# analog-fan-controller.net
KiCad netlist of a schematic drawn in EAGLE
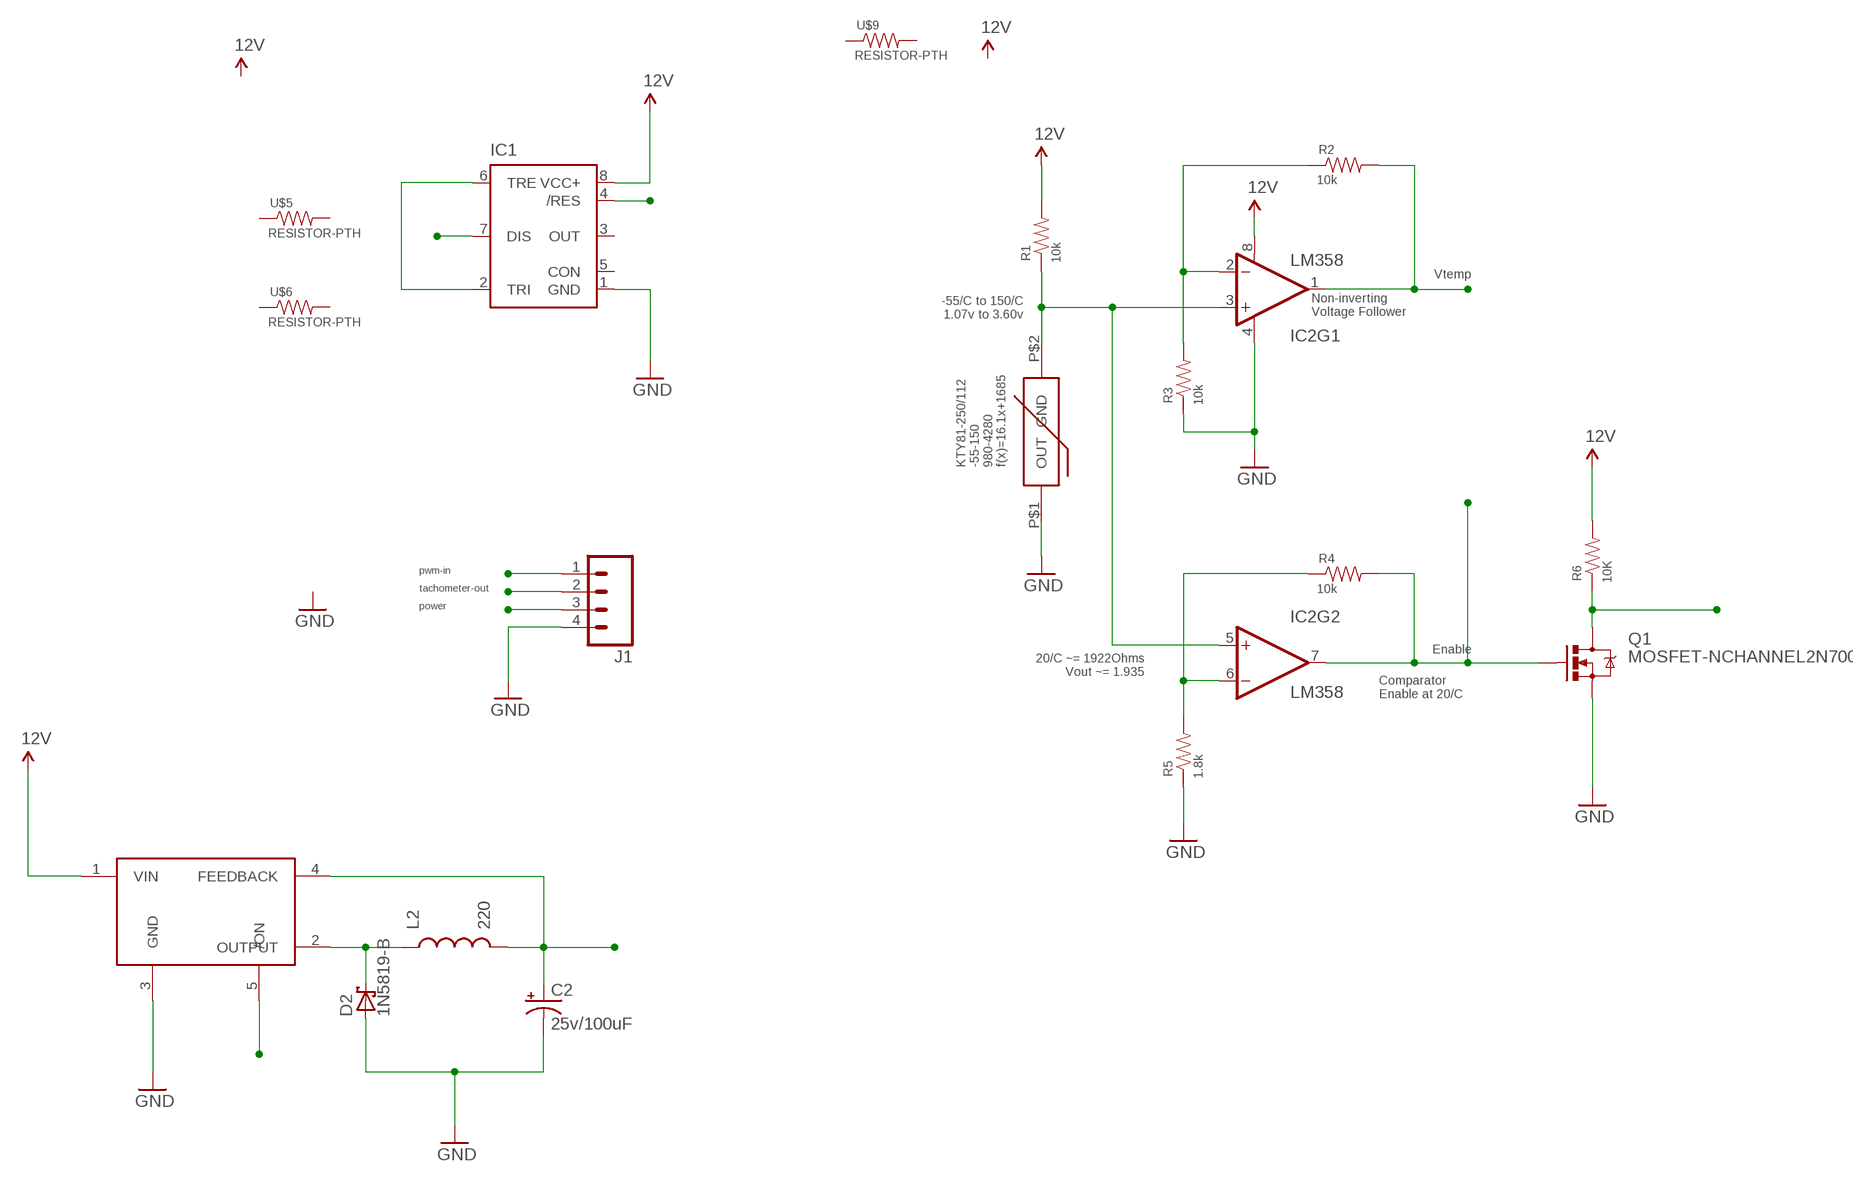
[diagram p0: schematic, sheet 1]

(export (version "E")
  (design (tool "Eeschema 10.0.6"))
  (components
    (comp (ref "C2")
      (value "25v/100uF")
      (footprint "eagle-import:CPOL-RADIAL-1000UF-25V")
      (libsource (lib "eagle-import") (part "1000UF-25V(PTH)"))
    )
    (comp (ref "D2")
      (value "1N5819-B")
      (footprint "eagle-import:DO41-7.6")
      (libsource (lib "eagle-import") (part "1N5819-B"))
    )
    (comp (ref "IC1")
      (value "NE555P")
      (footprint "eagle-import:DIL-08")
      (fields (field (name "MF") "Arrow Electronics") (field (name "MPN") "NE555N"))
      (libsource (lib "eagle-import") (part "NE555P"))
    )
    (comp (ref "IC2")
      (value "LM358")
      (footprint "eagle-import:DIP08")
      (libsource (lib "eagle-import") (part "LM358"))
    )
    (comp (ref "J1")
      (value "M04POLAR")
      (footprint "eagle-import:MOLEX-1X4")
      (libsource (lib "eagle-import") (part "M04POLAR"))
    )
    (comp (ref "L2")
      (value "220")
      (footprint "eagle-import:AXIAL-0.6")
      (libsource (lib "eagle-import") (part "INDUCTORAXIAL-0.6"))
    )
    (comp (ref "Q1")
      (value "MOSFET-NCHANNEL2N7000")
      (footprint "eagle-import:TO-92")
      (libsource (lib "eagle-import") (part "MOSFET-NCHANNEL2N7000"))
    )
    (comp (ref "R1")
      (value "10k")
      (footprint "eagle-import:VERT-PTH")
      (libsource (lib "eagle-import") (part "RESISTOR-PTH"))
    )
    (comp (ref "R2")
      (value "10k")
      (footprint "eagle-import:VERT-PTH")
      (libsource (lib "eagle-import") (part "RESISTOR-PTH"))
    )
    (comp (ref "R3")
      (value "10k")
      (footprint "eagle-import:VERT-PTH")
      (libsource (lib "eagle-import") (part "RESISTOR-PTH"))
    )
    (comp (ref "R4")
      (value "10k")
      (footprint "eagle-import:VERT-PTH")
      (libsource (lib "eagle-import") (part "RESISTOR-PTH"))
    )
    (comp (ref "R5")
      (value "1.8k")
      (footprint "eagle-import:VERT-PTH")
      (libsource (lib "eagle-import") (part "RESISTOR-PTH"))
    )
    (comp (ref "R6")
      (value "10K")
      (footprint "eagle-import:VERT-PTH")
      (libsource (lib "eagle-import") (part "RESISTOR-PTH"))
    )
    (comp (ref "RT")
      (value "980")
      (footprint "eagle-import:TO-92-2")
      (libsource (lib "eagle-import") (part "KTY81"))
    )
    (comp (ref "U$2")
      (value "LM2576XXVERTICAL")
      (footprint "eagle-import:TO-220-5")
      (libsource (lib "eagle-import") (part "LM2576XXVERTICAL"))
    )
    (comp (ref "U$5")
      (value "RESISTOR-PTH")
      (footprint "eagle-import:VERT-PTH")
      (libsource (lib "eagle-import") (part "RESISTOR-PTH"))
    )
    (comp (ref "U$6")
      (value "RESISTOR-PTH")
      (footprint "eagle-import:VERT-PTH")
      (libsource (lib "eagle-import") (part "RESISTOR-PTH"))
    )
    (comp (ref "U$9")
      (value "RESISTOR-PTH")
      (footprint "eagle-import:VERT-PTH")
      (libsource (lib "eagle-import") (part "RESISTOR-PTH"))
    )
  )
  (nets
    (net (code "1") (name "/ENABLE") (class "Default")
      (node (ref "IC1") (pin "4") (pinfunction "/RES_4") (pintype "input"))
      (node (ref "IC2") (pin "7") (pinfunction "OUT_7") (pintype "output"))
      (node (ref "Q1") (pin "2") (pinfunction "G_2") (pintype "passive"))
      (node (ref "R4") (pin "2") (pinfunction "G$2_2") (pintype "bidirectional"))
    )
    (net (code "2") (name "/FAN-POWER") (class "Default")
      (node (ref "C2") (pin "+") (pinfunction "+_+") (pintype "passive"))
      (node (ref "J1") (pin "3") (pinfunction "3_3") (pintype "passive"))
      (node (ref "L2") (pin "P$2") (pinfunction "2_P$2") (pintype "passive"))
      (node (ref "U$2") (pin "4") (pinfunction "FEEDBACK_4") (pintype "bidirectional"))
    )
    (net (code "3") (name "/POWER-ENABLE") (class "Default")
      (node (ref "Q1") (pin "3") (pinfunction "D_3") (pintype "passive"))
      (node (ref "R6") (pin "1") (pinfunction "G$1_1") (pintype "bidirectional"))
      (node (ref "U$2") (pin "5") (pinfunction "/ON_5") (pintype "bidirectional"))
    )
    (net (code "4") (name "12V") (class "Default")
      (node (ref "IC1") (pin "8") (pinfunction "VCC+_8") (pintype "power_in"))
      (node (ref "IC2") (pin "8") (pinfunction "V+_8") (pintype "power_in"))
      (node (ref "R1") (pin "2") (pinfunction "G$2_2") (pintype "bidirectional"))
      (node (ref "R6") (pin "2") (pinfunction "G$2_2") (pintype "bidirectional"))
      (node (ref "U$2") (pin "1") (pinfunction "VIN_1") (pintype "bidirectional"))
    )
    (net (code "5") (name "GND") (class "Default")
      (node (ref "C2") (pin "-") (pinfunction "-_-") (pintype "passive"))
      (node (ref "D2") (pin "A") (pinfunction "A_A") (pintype "passive"))
      (node (ref "IC1") (pin "1") (pinfunction "GND_1") (pintype "power_in"))
      (node (ref "IC2") (pin "4") (pinfunction "V-_4") (pintype "power_in"))
      (node (ref "J1") (pin "4") (pinfunction "4_4") (pintype "passive"))
      (node (ref "Q1") (pin "1") (pinfunction "S_1") (pintype "passive"))
      (node (ref "R3") (pin "1") (pinfunction "G$1_1") (pintype "bidirectional"))
      (node (ref "R5") (pin "1") (pinfunction "G$1_1") (pintype "bidirectional"))
      (node (ref "RT") (pin "P$1") (pinfunction "OUT_P$1") (pintype "bidirectional"))
      (node (ref "U$2") (pin "3") (pinfunction "GND_3") (pintype "bidirectional"))
    )
    (net (code "6") (name "Net-(IC1-TRE)") (class "Default")
      (node (ref "IC1") (pin "2") (pinfunction "TRI_2") (pintype "input"))
      (node (ref "IC1") (pin "6") (pinfunction "TRE_6") (pintype "input"))
    )
    (net (code "7") (name "Net-(IC2A-+IN)") (class "Default")
      (node (ref "IC2") (pin "3") (pinfunction "+IN_3") (pintype "input"))
      (node (ref "IC2") (pin "5") (pinfunction "+IN_5") (pintype "input"))
      (node (ref "R1") (pin "1") (pinfunction "G$1_1") (pintype "bidirectional"))
      (node (ref "RT") (pin "P$2") (pinfunction "GND_P$2") (pintype "bidirectional"))
    )
    (net (code "8") (name "Net-(IC2A--IN)") (class "Default")
      (node (ref "IC2") (pin "2") (pinfunction "-IN_2") (pintype "input"))
      (node (ref "R2") (pin "1") (pinfunction "G$1_1") (pintype "bidirectional"))
      (node (ref "R3") (pin "2") (pinfunction "G$2_2") (pintype "bidirectional"))
    )
    (net (code "9") (name "Net-(IC2A-OUT)") (class "Default")
      (node (ref "IC2") (pin "1") (pinfunction "OUT_1") (pintype "output"))
      (node (ref "R2") (pin "2") (pinfunction "G$2_2") (pintype "bidirectional"))
    )
    (net (code "10") (name "Net-(IC2B--IN)") (class "Default")
      (node (ref "IC2") (pin "6") (pinfunction "-IN_6") (pintype "input"))
      (node (ref "R4") (pin "1") (pinfunction "G$1_1") (pintype "bidirectional"))
      (node (ref "R5") (pin "2") (pinfunction "G$2_2") (pintype "bidirectional"))
    )
    (net (code "11") (name "Net-(L2-1)") (class "Default")
      (node (ref "D2") (pin "C") (pinfunction "C_C") (pintype "passive"))
      (node (ref "L2") (pin "P$1") (pinfunction "1_P$1") (pintype "passive"))
      (node (ref "U$2") (pin "2") (pinfunction "OUTPUT_2") (pintype "bidirectional"))
    )
    (net (code "12") (name "unconnected-(IC1-CON-Pad5)") (class "Default")
      (node (ref "IC1") (pin "5") (pinfunction "CON_5") (pintype "input"))
    )
    (net (code "13") (name "unconnected-(IC1-DIS-Pad7)") (class "Default")
      (node (ref "IC1") (pin "7") (pinfunction "DIS_7") (pintype "input"))
    )
    (net (code "14") (name "unconnected-(IC1-OUT-Pad3)") (class "Default")
      (node (ref "IC1") (pin "3") (pinfunction "OUT_3") (pintype "output"))
    )
    (net (code "15") (name "unconnected-(J1-Pad1)") (class "Default")
      (node (ref "J1") (pin "1") (pinfunction "1_1") (pintype "passive"))
    )
    (net (code "16") (name "unconnected-(J1-Pad2)") (class "Default")
      (node (ref "J1") (pin "2") (pinfunction "2_2") (pintype "passive"))
    )
    (net (code "17") (name "unconnected-(U$5-G$1-Pad1)") (class "Default")
      (node (ref "U$5") (pin "1") (pinfunction "G$1_1") (pintype "bidirectional"))
    )
    (net (code "18") (name "unconnected-(U$5-G$2-Pad2)") (class "Default")
      (node (ref "U$5") (pin "2") (pinfunction "G$2_2") (pintype "bidirectional"))
    )
    (net (code "19") (name "unconnected-(U$6-G$1-Pad1)") (class "Default")
      (node (ref "U$6") (pin "1") (pinfunction "G$1_1") (pintype "bidirectional"))
    )
    (net (code "20") (name "unconnected-(U$6-G$2-Pad2)") (class "Default")
      (node (ref "U$6") (pin "2") (pinfunction "G$2_2") (pintype "bidirectional"))
    )
    (net (code "21") (name "unconnected-(U$9-G$1-Pad1)") (class "Default")
      (node (ref "U$9") (pin "1") (pinfunction "G$1_1") (pintype "bidirectional"))
    )
    (net (code "22") (name "unconnected-(U$9-G$2-Pad2)") (class "Default")
      (node (ref "U$9") (pin "2") (pinfunction "G$2_2") (pintype "bidirectional"))
    )
  )
)
